# ldo1_1.net
KiCad netlist of a schematic drawn in Altium Designer
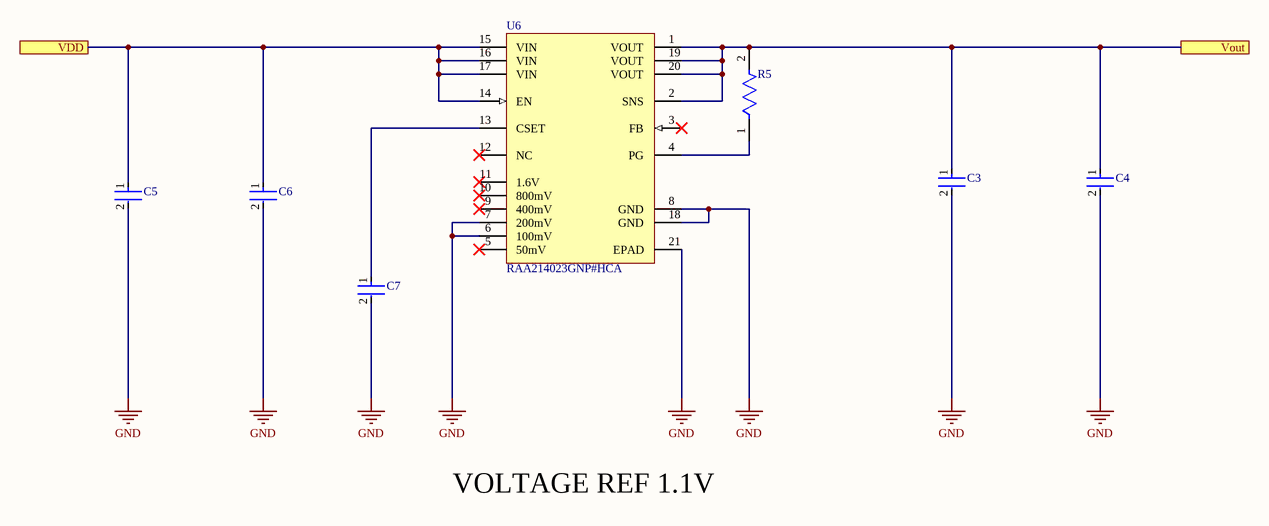
[diagram p0: ldo1.1.SchDoc]

(export (version "E")
  (design (tool "Eeschema 10.0.6"))
  (components
    (comp (ref "C3")
      (value "CL21A226MOCLRNC")
      (footprint "FP-CL21-IPC_C")
      (description "CL21 Series 0805 22uF 16V ±20% Tolerance X5R Multilayer Ceramic Chip Capacitor")
      (fields (field (name "TOLERANCE") "20%"))
      (libsource (lib "Altium Content Vault") (part "b4654b650e69147ec39a6b967a45e02"))
    )
    (comp (ref "C4")
      (value "C0805C104K4RAC")
      (footprint "FP-C0805C-DN-MFG")
      (description "C0805 0.10 μF X7R 30ppm/°C 10.00% 16 V")
      (fields
        (field (name "TOLERANCE") "0.1")
        (field (name "OCTOPART") "https://octopart.com/c0805c104k4rac-kemet-1343167")
      )
      (libsource (lib "Altium Content Vault") (part "b4654b650e69147ec39a6b967a45e02"))
    )
    (comp (ref "C5")
      (value "0.1 uF C0805C104K4RAC")
      (footprint "FP-C0805C-DN-MFG")
      (description "C0805 0.10 μF X7R 30ppm/°C 10.00% 16 V\r\nC0805C104K4RAC")
      (fields
        (field (name "TOLERANCE") "0.1")
        (field (name "OCTOPART") "https://octopart.com/c0805c104k4rac-kemet-1343167")
      )
      (libsource (lib "Altium Content Vault") (part "b4654b650e69147ec39a6b967a45e02"))
    )
    (comp (ref "C6")
      (value "CL21A106KOQNNNG")
      (footprint "FP-CL21-IPC_C")
      (description "CL21 Series 0805 10uF 16V ±10% Tolerance X5R Multilayer Ceramic Chip Capacitor")
      (fields (field (name "TOLERANCE") "10%") (field (name "VOLTAGE") "16V"))
      (libsource (lib "Altium Content Vault") (part "b4654b650e69147ec39a6b967a45e02"))
    )
    (comp (ref "C7")
      (value "C0805C104K4RAC")
      (footprint "FP-C0805C-DN-MFG")
      (description "C0805 0.10 μF X7R 30ppm/°C 10.00% 16 V")
      (fields
        (field (name "TOLERANCE") "0.1")
        (field (name "OCTOPART") "https://octopart.com/c0805c104k4rac-kemet-1343167")
      )
      (libsource (lib "Altium Content Vault") (part "b4654b650e69147ec39a6b967a45e02"))
    )
    (comp (ref "R5")
      (value "RC1005F103CS")
      (footprint "FP-RC1005-IPC_B")
      (description "Res Thick Film 0402 10kΩ 1% 0.063W ±100ppm/°C Molded SMD T/R")
      (fields (field (name "TOLERANCE") "1%"))
      (libsource (lib "Altium Content Vault") (part "1029c3af85768c4190bb7ad29bc67b5"))
    )
    (comp (ref "U6")
      (value "RAA214023GNP#HCA")
      (footprint "L20_3_5x3_5_MFG")
      (description "LDO Voltage Regulators 2A Low Noise LDO, 20 Lead 3.5x3.5 QFN (NiPdAu-Ag lead finish")
      (libsource (lib "Altium Content Vault") (part "bad0c6e7bfbbda4230ff4fb28f5c8c7"))
    )
  )
  (nets
    (net (code "1") (name "/VDD") (class "Default")
      (node (ref "C5") (pin "1") (pinfunction "1_1") (pintype "passive"))
      (node (ref "C6") (pin "1") (pinfunction "1_1") (pintype "passive"))
      (node (ref "U6") (pin "14") (pinfunction "EN_14") (pintype "input"))
      (node (ref "U6") (pin "15") (pinfunction "VIN_15") (pintype "power_in"))
      (node (ref "U6") (pin "16") (pinfunction "VIN_16") (pintype "power_in"))
      (node (ref "U6") (pin "17") (pinfunction "VIN_17") (pintype "power_in"))
    )
    (net (code "2") (name "/Vout") (class "Default")
      (node (ref "C3") (pin "1") (pinfunction "1_1") (pintype "passive"))
      (node (ref "C4") (pin "1") (pinfunction "1_1") (pintype "passive"))
      (node (ref "R5") (pin "2") (pinfunction "2_2") (pintype "passive"))
      (node (ref "U6") (pin "1") (pinfunction "VOUT_1") (pintype "power_in"))
      (node (ref "U6") (pin "19") (pinfunction "VOUT_19") (pintype "power_in"))
      (node (ref "U6") (pin "2") (pinfunction "SNS_2") (pintype "passive"))
      (node (ref "U6") (pin "20") (pinfunction "VOUT_20") (pintype "power_in"))
    )
    (net (code "3") (name "GND") (class "Default")
      (node (ref "C3") (pin "2") (pinfunction "2_2") (pintype "passive"))
      (node (ref "C4") (pin "2") (pinfunction "2_2") (pintype "passive"))
      (node (ref "C5") (pin "2") (pinfunction "2_2") (pintype "passive"))
      (node (ref "C6") (pin "2") (pinfunction "2_2") (pintype "passive"))
      (node (ref "C7") (pin "2") (pinfunction "2_2") (pintype "passive"))
      (node (ref "U6") (pin "18") (pinfunction "GND_18") (pintype "power_in"))
      (node (ref "U6") (pin "21") (pinfunction "EPAD_21") (pintype "power_in"))
      (node (ref "U6") (pin "6") (pinfunction "100mV_6") (pintype "power_in"))
      (node (ref "U6") (pin "7") (pinfunction "200mV_7") (pintype "power_in"))
      (node (ref "U6") (pin "8") (pinfunction "GND_8") (pintype "power_in"))
    )
    (net (code "4") (name "Net-(U6-CSET)") (class "Default")
      (node (ref "C7") (pin "1") (pinfunction "1_1") (pintype "passive"))
      (node (ref "U6") (pin "13") (pinfunction "CSET_13") (pintype "passive"))
    )
    (net (code "5") (name "Net-(U6-PG)") (class "Default")
      (node (ref "R5") (pin "1") (pinfunction "1_1") (pintype "passive"))
      (node (ref "U6") (pin "4") (pinfunction "PG_4") (pintype "open_collector"))
    )
    (net (code "6") (name "unconnected-(U6-1.6V-Pad11)") (class "Default")
      (node (ref "U6") (pin "11") (pinfunction "1.6V_11") (pintype "power_in+no_connect"))
    )
    (net (code "7") (name "unconnected-(U6-50mV-Pad5)") (class "Default")
      (node (ref "U6") (pin "5") (pinfunction "50mV_5") (pintype "power_in+no_connect"))
    )
    (net (code "8") (name "unconnected-(U6-400mV-Pad9)") (class "Default")
      (node (ref "U6") (pin "9") (pinfunction "400mV_9") (pintype "power_in+no_connect"))
    )
    (net (code "9") (name "unconnected-(U6-800mV-Pad10)") (class "Default")
      (node (ref "U6") (pin "10") (pinfunction "800mV_10") (pintype "power_in+no_connect"))
    )
    (net (code "10") (name "unconnected-(U6-FB-Pad3)") (class "Default")
      (node (ref "U6") (pin "3") (pinfunction "FB_3") (pintype "input+no_connect"))
    )
    (net (code "11") (name "unconnected-(U6-NC-Pad12)") (class "Default")
      (node (ref "U6") (pin "12") (pinfunction "NC_12") (pintype "passive+no_connect"))
    )
  )
)
